# SCNUC51V2.net
KiCad netlist of a schematic drawn in Altium Designer
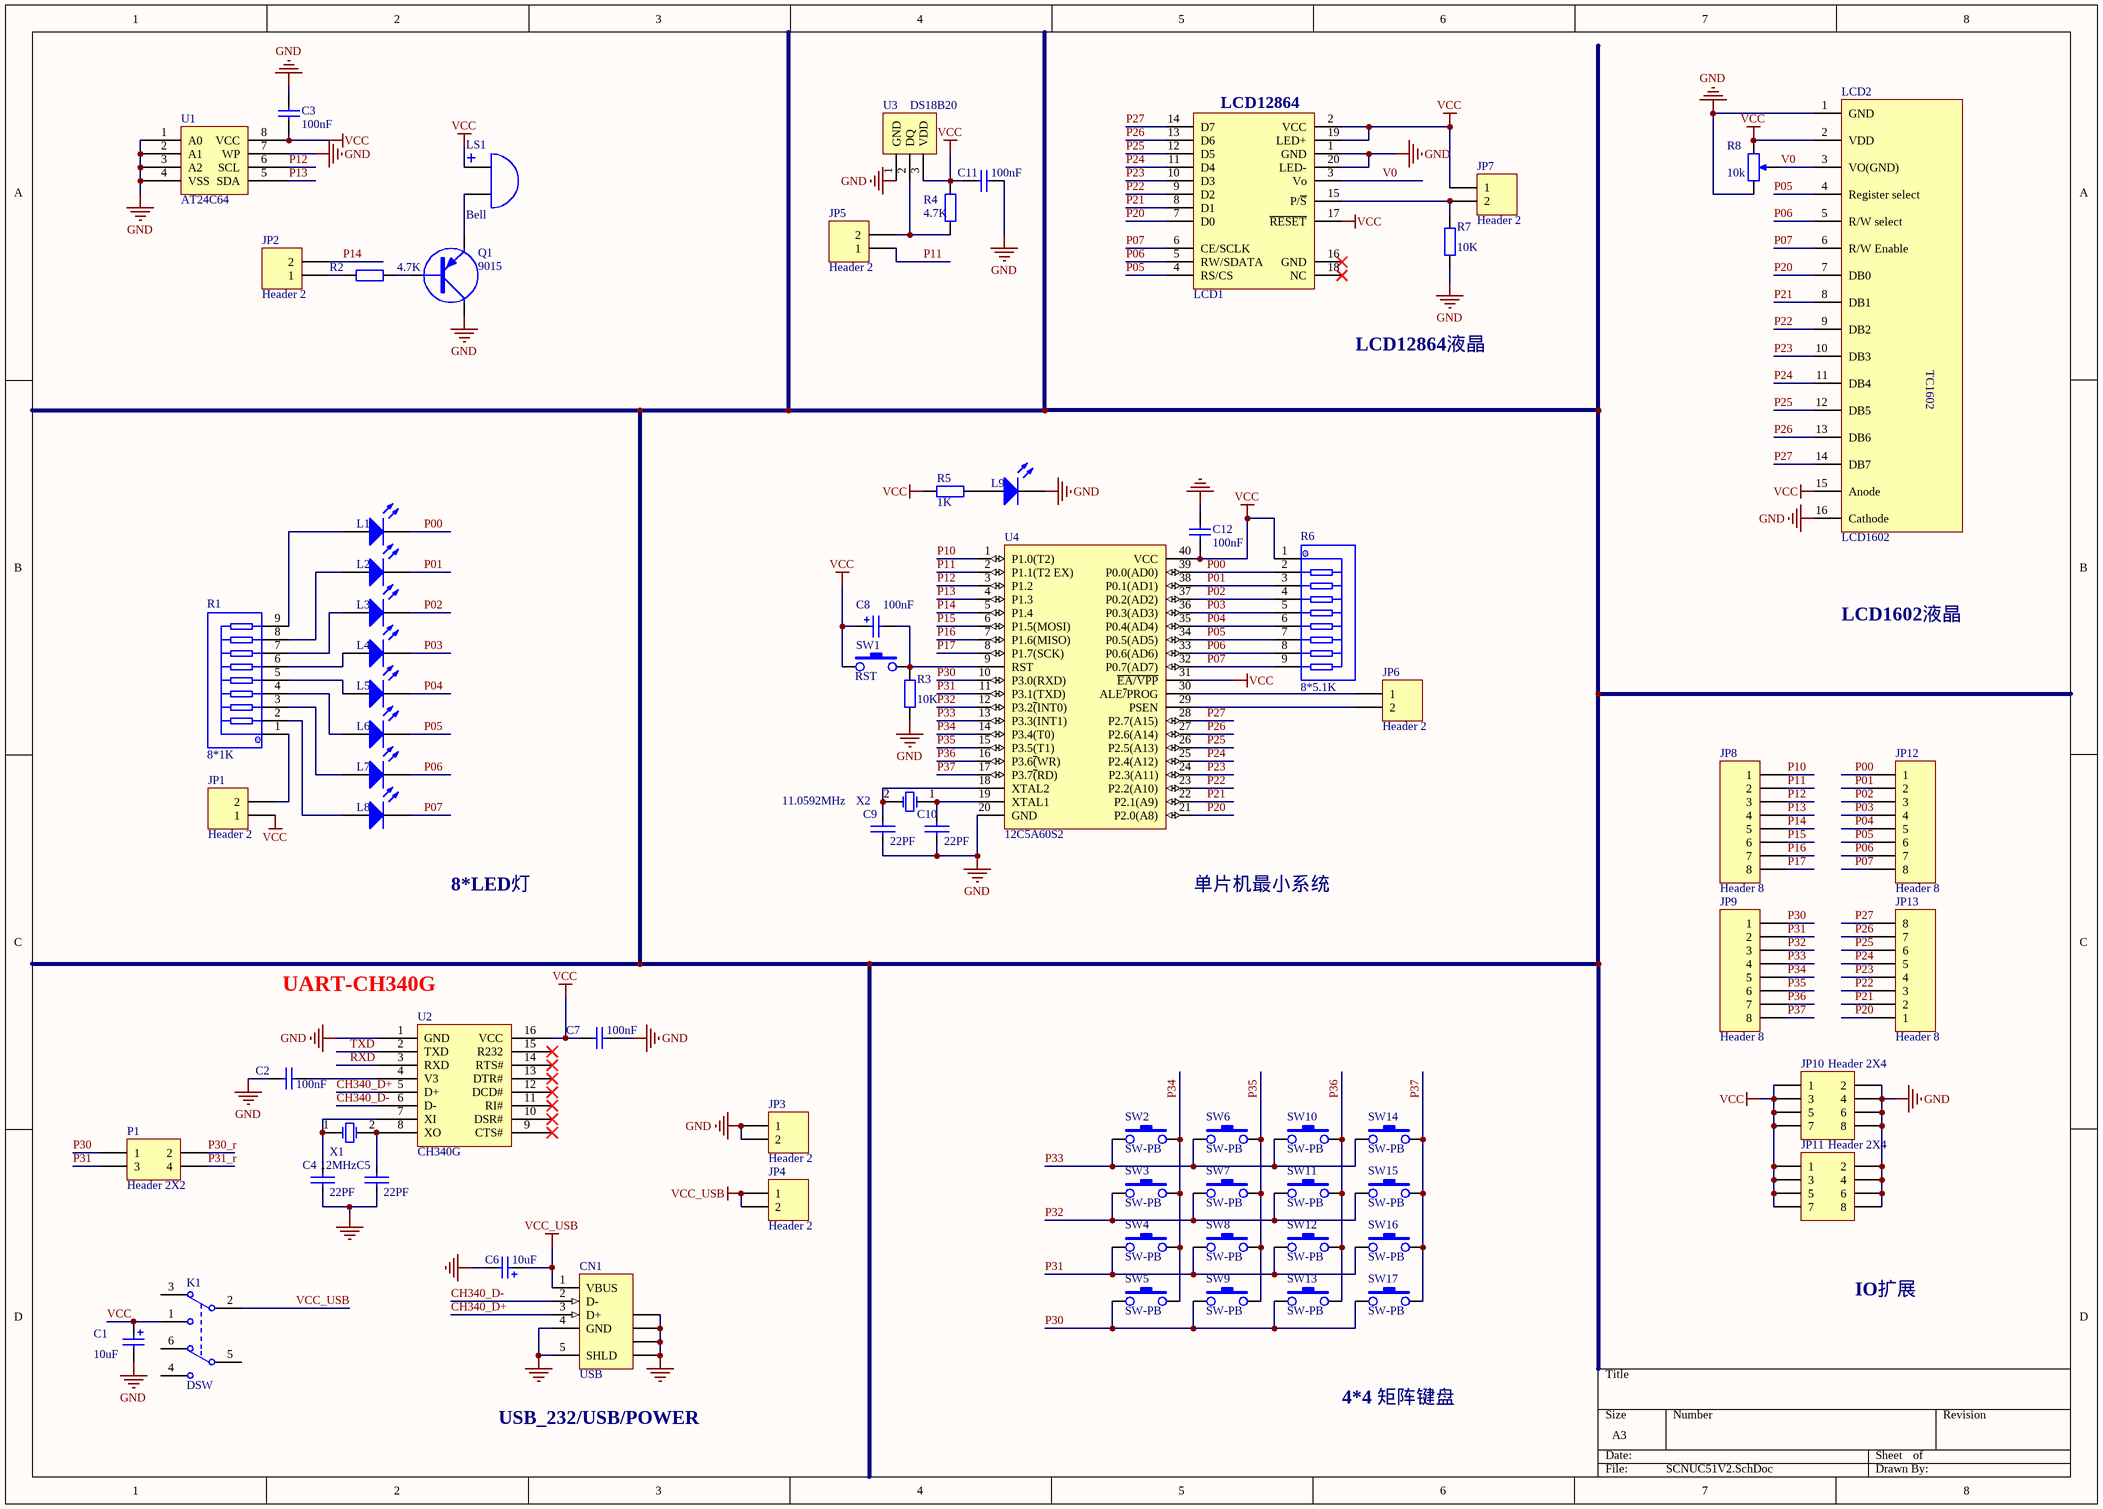
[diagram p0: SCNUC51V2.SchDoc]

(export (version "E")
  (design (tool "Eeschema 10.0.6"))
  (components
    (comp (ref "C1")
      (value "10uF")
      (footprint "hecheng:RB0.1-0.2")
      (description "Capacitor")
      (fields
        (field (name "MANUFACTURER") "Generic Components")
        (field (name "Comment") "Cap")
        (field (name "PUBLISHER") "Altium Hobart Technology Centre")
      )
      (libsource (lib "hecheng") (part "Cap Pol1"))
    )
    (comp (ref "C2")
      (value "100nF")
      (footprint "C0805")
      (description "Capacitor")
      (fields (field (name "Comment") "Cap"))
      (libsource (lib "Myself") (part "Cap"))
    )
    (comp (ref "C3")
      (value "100nF")
      (footprint "C0805")
      (description "Capacitor")
      (fields (field (name "Comment") "Cap"))
      (libsource (lib "Myself") (part "Cap"))
    )
    (comp (ref "C4")
      (value "22PF")
      (footprint "C0805")
      (description "Capacitor")
      (fields (field (name "Comment") "CAP"))
      (libsource (lib "hecheng") (part "CAP"))
    )
    (comp (ref "C5")
      (value "22PF")
      (footprint "C0805")
      (description "Capacitor")
      (fields (field (name "Comment") "CAP"))
      (libsource (lib "hecheng") (part "CAP"))
    )
    (comp (ref "C6")
      (value "10uF")
      (footprint "RB0.1-0.2")
      (description "Capacitor")
      (fields
        (field (name "MANUFACTURER") "Generic Components")
        (field (name "Comment") "Cap")
        (field (name "PUBLISHER") "Altium Hobart Technology Centre")
      )
      (libsource (lib "hecheng") (part "Cap Pol1"))
    )
    (comp (ref "C7")
      (value "100nF")
      (footprint "C0805")
      (description "Capacitor")
      (fields (field (name "Comment") "Cap"))
      (libsource (lib "Myself") (part "Cap"))
    )
    (comp (ref "C8")
      (value "100nF")
      (footprint "C0805")
      (description "Capacitor")
      (fields
        (field (name "MANUFACTURER") "Generic Components")
        (field (name "Comment") "CAP")
        (field (name "PUBLISHER") "Altium Hobart Technology Centre")
      )
      (libsource (lib "hecheng") (part "Cap Pol1"))
    )
    (comp (ref "C9")
      (value "22PF")
      (footprint "C0805")
      (description "Capacitor")
      (fields (field (name "Comment") "CAP"))
      (libsource (lib "hecheng") (part "CAP"))
    )
    (comp (ref "C10")
      (value "22PF")
      (footprint "C0805")
      (description "Capacitor")
      (fields (field (name "Comment") "CAP"))
      (libsource (lib "hecheng") (part "CAP"))
    )
    (comp (ref "C11")
      (value "100nF")
      (footprint "C0805")
      (description "Capacitor")
      (fields (field (name "Comment") "Cap"))
      (libsource (lib "Myself") (part "Cap"))
    )
    (comp (ref "C12")
      (value "100nF")
      (footprint "C0805")
      (description "Capacitor")
      (fields (field (name "Comment") "Cap"))
      (libsource (lib "Myself") (part "Cap"))
    )
    (comp (ref "CN1")
      (value "USB")
      (footprint "USB-mini")
      (description "USB MINI")
      (fields (field (name "PUBLISHER") "Altium Limited"))
      (libsource (lib "AMP Serial Bus USB") (part "440479-1"))
    )
    (comp (ref "JP1")
      (value "Header 2")
      (footprint "HDR1X2")
      (description "Header, 2-Pin")
      (fields (field (name "PUBLISHER") "Altium Limited"))
      (libsource (lib "") (part "Header 2_1"))
    )
    (comp (ref "JP2")
      (value "Header 2")
      (footprint "HDR1X2")
      (description "Header, 2-Pin")
      (fields (field (name "PUBLISHER") "Altium Limited"))
      (libsource (lib "") (part "Header 2_1"))
    )
    (comp (ref "JP3")
      (value "Header 2")
      (footprint "HDR1X2")
      (description "Header, 2-Pin")
      (fields (field (name "PUBLISHER") "Altium Limited"))
      (libsource (lib "hecheng") (part "Header 2"))
    )
    (comp (ref "JP4")
      (value "Header 2")
      (footprint "HDR1X2")
      (description "Header, 2-Pin")
      (fields (field (name "PUBLISHER") "Altium Limited"))
      (libsource (lib "hecheng") (part "Header 2"))
    )
    (comp (ref "JP5")
      (value "Header 2")
      (footprint "HDR1X2")
      (description "Header, 2-Pin")
      (fields (field (name "PUBLISHER") "Altium Limited"))
      (libsource (lib "") (part "Header 2_1"))
    )
    (comp (ref "JP6")
      (value "Header 2")
      (footprint "HDR1X2")
      (description "Header, 2-Pin")
      (fields (field (name "PUBLISHER") "Altium Limited"))
      (libsource (lib "hecheng") (part "Header 2"))
    )
    (comp (ref "JP7")
      (value "Header 2")
      (footprint "HDR1X2")
      (description "Header, 2-Pin")
      (fields (field (name "PUBLISHER") "Altium Limited"))
      (libsource (lib "hecheng") (part "Header 2"))
    )
    (comp (ref "JP8")
      (value "Header 8")
      (footprint "HDR1X8")
      (description "Header, 8-Pin")
      (fields (field (name "PUBLISHER") "Altium Limited"))
      (libsource (lib "") (part "Header 8_2"))
    )
    (comp (ref "JP9")
      (value "Header 8")
      (footprint "HDR1X8")
      (description "Header, 8-Pin")
      (fields (field (name "PUBLISHER") "Altium Limited"))
      (libsource (lib "") (part "Header 8_2"))
    )
    (comp (ref "JP10")
      (value "Header 2X4")
      (footprint "HDR2-4")
      (description "Header, 4-Pin, Dual row")
      (fields (field (name "MANUFACTURER") "Generic Components"))
      (libsource (lib "hecheng") (part "Header 2X4"))
    )
    (comp (ref "JP11")
      (value "Header 2X4")
      (footprint "HDR2-4")
      (description "Header, 4-Pin, Dual row")
      (fields (field (name "MANUFACTURER") "Generic Components"))
      (libsource (lib "hecheng") (part "Header 2X4"))
    )
    (comp (ref "JP12")
      (value "Header 8")
      (footprint "HDR1X8")
      (description "Header, 8-Pin")
      (fields (field (name "PUBLISHER") "Altium Limited"))
      (libsource (lib "") (part "Header 8_1"))
    )
    (comp (ref "JP13")
      (value "Header 8")
      (footprint "HDR1X8")
      (description "Header, 8-Pin")
      (fields (field (name "PUBLISHER") "Altium Limited"))
      (libsource (lib "hecheng") (part "Header 8"))
    )
    (comp (ref "K1") (value "DSW") (footprint "DPDT-6") (libsource (lib "hecheng") (part "DSW")))
    (comp (ref "L1") (value "LED") (footprint "LED-3MM") (libsource (lib "hecheng") (part "LED-3MM")))
    (comp (ref "L2") (value "LED") (footprint "LED-3MM") (libsource (lib "hecheng") (part "LED-3MM")))
    (comp (ref "L3") (value "LED") (footprint "LED-3MM") (libsource (lib "hecheng") (part "LED-3MM")))
    (comp (ref "L4") (value "LED") (footprint "LED-3MM") (libsource (lib "hecheng") (part "LED-3MM")))
    (comp (ref "L5") (value "LED") (footprint "LED-3MM") (libsource (lib "hecheng") (part "LED-3MM")))
    (comp (ref "L6") (value "LED") (footprint "LED-3MM") (libsource (lib "hecheng") (part "LED-3MM")))
    (comp (ref "L7") (value "LED") (footprint "LED-3MM") (libsource (lib "hecheng") (part "LED-3MM")))
    (comp (ref "L8") (value "LED") (footprint "LED-3MM") (libsource (lib "hecheng") (part "LED-3MM")))
    (comp (ref "L9") (value "LED") (footprint "LED-3MM") (libsource (lib "hecheng") (part "LED-3MM")))
    (comp (ref "LCD1")
      (value "LCD12864")
      (footprint "LCD12864F")
      (libsource (lib "SXF'S LIB") (part "LCD12864"))
    )
    (comp (ref "LCD2") (value "LCD1602") (footprint "LCD1602") (libsource (lib "hecheng") (part "LCD1602")))
    (comp (ref "LS1")
      (value "Bell")
      (footprint "BELL0.3-0.46")
      (description "Electrical Bell")
      (fields (field (name "MANUFACTURER") "Generic Components"))
      (libsource (lib "hecheng") (part "Bell"))
    )
    (comp (ref "P1")
      (value "Header 2X2")
      (footprint "HDR2X2")
      (description "Header, 2-Pin, Dual row")
      (fields (field (name "PUBLISHER") "Altium Limited"))
      (libsource (lib "Miscellaneous Connectors") (part "Header 2X2"))
    )
    (comp (ref "Q1")
      (value "9015")
      (footprint "TO-92")
      (description "PNP")
      (libsource (lib "hecheng") (part "9015"))
    )
    (comp (ref "R1")
      (value "8*1K")
      (footprint "PIN-9")
      (description "Resistor Array")
      (fields (field (name "Comment") "RES-8"))
      (libsource (lib "hecheng") (part "RES-8"))
    )
    (comp (ref "R2")
      (value "4.7K")
      (footprint "SXF'S LIB:R0805")
      (description "Resistor")
      (fields
        (field (name "MANUFACTURER") "Generic Components")
        (field (name "Comment") "Res")
        (field (name "PUBLISHER") "Altium Hobart Technology Centre")
      )
      (libsource (lib "hecheng") (part "Res"))
    )
    (comp (ref "R3")
      (value "10K")
      (footprint "hecheng:R0805")
      (description "Resistor")
      (fields
        (field (name "MANUFACTURER") "Generic Components")
        (field (name "Comment") "Res")
        (field (name "PUBLISHER") "Altium Hobart Technology Centre")
      )
      (libsource (lib "") (part "Res_1"))
    )
    (comp (ref "R4")
      (value "4.7K")
      (footprint "R0805")
      (description "Resistor")
      (fields
        (field (name "MANUFACTURER") "Generic Components")
        (field (name "Comment") "Res")
        (field (name "PUBLISHER") "Altium Hobart Technology Centre")
      )
      (libsource (lib "") (part "Res_2"))
    )
    (comp (ref "R5")
      (value "1K")
      (footprint "R0805")
      (description "Resistor")
      (fields
        (field (name "MANUFACTURER") "Generic Components")
        (field (name "Comment") "Res")
        (field (name "PUBLISHER") "Altium Hobart Technology Centre")
      )
      (libsource (lib "hecheng") (part "Res"))
    )
    (comp (ref "R6")
      (value "8*5.1K")
      (footprint "PIN-9")
      (description "Resistor Array")
      (fields (field (name "Comment") "RES-8"))
      (libsource (lib "hecheng") (part "RES-8"))
    )
    (comp (ref "R7")
      (value "10K")
      (footprint "hecheng:R0805")
      (description "Resistor")
      (fields
        (field (name "MANUFACTURER") "Generic Components")
        (field (name "Comment") "Res")
        (field (name "PUBLISHER") "Altium Hobart Technology Centre")
      )
      (libsource (lib "") (part "Res_1"))
    )
    (comp (ref "R8")
      (value "10k")
      (footprint "hecheng:VR-Z")
      (description "Potentiometer")
      (fields (field (name "Comment") "RES-Pot2"))
      (libsource (lib "hecheng") (part "RES-Pot2"))
    )
    (comp (ref "SW1")
      (value "RST")
      (footprint "SW1")
      (description "Button")
      (libsource (lib "hecheng") (part "SW-PB"))
    )
    (comp (ref "SW2") (value "SW-PB") (footprint "SW1") (libsource (lib "hecheng") (part "SW-PB")))
    (comp (ref "SW3") (value "SW-PB") (footprint "SW1") (libsource (lib "hecheng") (part "SW-PB")))
    (comp (ref "SW4") (value "SW-PB") (footprint "SW1") (libsource (lib "hecheng") (part "SW-PB")))
    (comp (ref "SW5") (value "SW-PB") (footprint "SW1") (libsource (lib "hecheng") (part "SW-PB")))
    (comp (ref "SW6") (value "SW-PB") (footprint "SW1") (libsource (lib "hecheng") (part "SW-PB")))
    (comp (ref "SW7") (value "SW-PB") (footprint "SW1") (libsource (lib "hecheng") (part "SW-PB")))
    (comp (ref "SW8") (value "SW-PB") (footprint "SW1") (libsource (lib "hecheng") (part "SW-PB")))
    (comp (ref "SW9") (value "SW-PB") (footprint "SW1") (libsource (lib "hecheng") (part "SW-PB")))
    (comp (ref "SW10") (value "SW-PB") (footprint "SW1") (libsource (lib "hecheng") (part "SW-PB")))
    (comp (ref "SW11") (value "SW-PB") (footprint "SW1") (libsource (lib "hecheng") (part "SW-PB")))
    (comp (ref "SW12") (value "SW-PB") (footprint "SW1") (libsource (lib "hecheng") (part "SW-PB")))
    (comp (ref "SW13") (value "SW-PB") (footprint "SW1") (libsource (lib "hecheng") (part "SW-PB")))
    (comp (ref "SW14") (value "SW-PB") (footprint "SW1") (libsource (lib "hecheng") (part "SW-PB")))
    (comp (ref "SW15") (value "SW-PB") (footprint "SW1") (libsource (lib "hecheng") (part "SW-PB")))
    (comp (ref "SW16") (value "SW-PB") (footprint "SW1") (libsource (lib "hecheng") (part "SW-PB")))
    (comp (ref "SW17") (value "SW-PB") (footprint "SW1") (libsource (lib "hecheng") (part "SW-PB")))
    (comp (ref "U1") (value "AT24C64") (footprint "DIP-8") (libsource (lib "hecheng") (part "AT24C64")))
    (comp (ref "U2")
      (value "CH340G")
      (footprint "SOP-127-16M")
      (description "USBtoUART")
      (libsource (lib "Myself") (part "CH340G"))
    )
    (comp (ref "U3")
      (value "DS18B20")
      (footprint "BCY-3")
      (description "Programmable Resolution\r\n1-Wire Digital Thermometer")
      (libsource (lib "hecheng") (part "DS18B20"))
    )
    (comp (ref "U4") (value "12C5A60S2") (footprint "DIP-40") (libsource (lib "hecheng") (part "89c51")))
    (comp (ref "X1")
      (value "12MHz")
      (footprint "XTAL")
      (description "XTAL")
      (libsource (lib "Myself") (part "XTAL"))
    )
    (comp (ref "X2")
      (value "11.0592MHz")
      (footprint "XTAL")
      (fields (field (name "Comment") "XTAL"))
      (libsource (lib "hecheng") (part "XTAL"))
    )
  )
  (nets
    (net (code "1") (name "/CH340_D+") (class "Default")
      (node (ref "CN1") (pin "3") (pinfunction "D+_3") (pintype "input"))
      (node (ref "U2") (pin "5") (pinfunction "D+_5") (pintype "passive"))
    )
    (net (code "2") (name "/CH340_D-") (class "Default")
      (node (ref "CN1") (pin "2") (pinfunction "D-_2") (pintype "input"))
      (node (ref "U2") (pin "6") (pinfunction "D-_6") (pintype "passive"))
    )
    (net (code "3") (name "/P00") (class "Default")
      (node (ref "JP12") (pin "1") (pinfunction "1_1") (pintype "passive"))
      (node (ref "L1") (pin "2") (pinfunction "K_2") (pintype "passive"))
      (node (ref "R6") (pin "2") (pinfunction "2_2") (pintype "passive"))
      (node (ref "U4") (pin "39") (pinfunction "P0.0(AD0)_39") (pintype "bidirectional"))
    )
    (net (code "4") (name "/P01") (class "Default")
      (node (ref "JP12") (pin "2") (pinfunction "2_2") (pintype "passive"))
      (node (ref "L2") (pin "2") (pinfunction "K_2") (pintype "passive"))
      (node (ref "R6") (pin "3") (pinfunction "3_3") (pintype "passive"))
      (node (ref "U4") (pin "38") (pinfunction "P0.1(AD1)_38") (pintype "bidirectional"))
    )
    (net (code "5") (name "/P02") (class "Default")
      (node (ref "JP12") (pin "3") (pinfunction "3_3") (pintype "passive"))
      (node (ref "L3") (pin "2") (pinfunction "K_2") (pintype "passive"))
      (node (ref "R6") (pin "4") (pinfunction "4_4") (pintype "passive"))
      (node (ref "U4") (pin "37") (pinfunction "P0.2(AD2)_37") (pintype "bidirectional"))
    )
    (net (code "6") (name "/P03") (class "Default")
      (node (ref "JP12") (pin "4") (pinfunction "4_4") (pintype "passive"))
      (node (ref "L4") (pin "2") (pinfunction "K_2") (pintype "passive"))
      (node (ref "R6") (pin "5") (pinfunction "5_5") (pintype "passive"))
      (node (ref "U4") (pin "36") (pinfunction "P0.3(AD3)_36") (pintype "bidirectional"))
    )
    (net (code "7") (name "/P04") (class "Default")
      (node (ref "JP12") (pin "5") (pinfunction "5_5") (pintype "passive"))
      (node (ref "L5") (pin "2") (pinfunction "K_2") (pintype "passive"))
      (node (ref "R6") (pin "6") (pinfunction "6_6") (pintype "passive"))
      (node (ref "U4") (pin "35") (pinfunction "P0.4(AD4)_35") (pintype "bidirectional"))
    )
    (net (code "8") (name "/P05") (class "Default")
      (node (ref "JP12") (pin "6") (pinfunction "6_6") (pintype "passive"))
      (node (ref "L6") (pin "2") (pinfunction "K_2") (pintype "passive"))
      (node (ref "LCD1") (pin "4") (pinfunction "RS/CS_4") (pintype "passive"))
      (node (ref "LCD2") (pin "4") (pinfunction "Register_select_4") (pintype "passive"))
      (node (ref "R6") (pin "7") (pinfunction "7_7") (pintype "passive"))
      (node (ref "U4") (pin "34") (pinfunction "P0.5(AD5)_34") (pintype "bidirectional"))
    )
    (net (code "9") (name "/P06") (class "Default")
      (node (ref "JP12") (pin "7") (pinfunction "7_7") (pintype "passive"))
      (node (ref "L7") (pin "2") (pinfunction "K_2") (pintype "passive"))
      (node (ref "LCD1") (pin "5") (pinfunction "RW/SDATA_5") (pintype "passive"))
      (node (ref "LCD2") (pin "5") (pinfunction "R/W_select_5") (pintype "passive"))
      (node (ref "R6") (pin "8") (pinfunction "8_8") (pintype "passive"))
      (node (ref "U4") (pin "33") (pinfunction "P0.6(AD6)_33") (pintype "bidirectional"))
    )
    (net (code "10") (name "/P07") (class "Default")
      (node (ref "JP12") (pin "8") (pinfunction "8_8") (pintype "passive"))
      (node (ref "L8") (pin "2") (pinfunction "K_2") (pintype "passive"))
      (node (ref "LCD1") (pin "6") (pinfunction "CE/SCLK_6") (pintype "passive"))
      (node (ref "LCD2") (pin "6") (pinfunction "R/W_Enable_6") (pintype "passive"))
      (node (ref "R6") (pin "9") (pinfunction "9_9") (pintype "passive"))
      (node (ref "U4") (pin "32") (pinfunction "P0.7(AD7)_32") (pintype "bidirectional"))
    )
    (net (code "11") (name "/P10") (class "Default")
      (node (ref "JP8") (pin "1") (pinfunction "1_1") (pintype "passive"))
      (node (ref "U4") (pin "1") (pinfunction "P1.0(T2)_1") (pintype "bidirectional"))
    )
    (net (code "12") (name "/P11") (class "Default")
      (node (ref "JP5") (pin "1") (pinfunction "1_1") (pintype "passive"))
      (node (ref "JP8") (pin "2") (pinfunction "2_2") (pintype "passive"))
      (node (ref "U4") (pin "2") (pinfunction "P1.1(T2_EX)_2") (pintype "bidirectional"))
    )
    (net (code "13") (name "/P12") (class "Default")
      (node (ref "JP8") (pin "3") (pinfunction "3_3") (pintype "passive"))
      (node (ref "U1") (pin "6") (pinfunction "SCL_6") (pintype "passive"))
      (node (ref "U4") (pin "3") (pinfunction "P1.2_3") (pintype "bidirectional"))
    )
    (net (code "14") (name "/P13") (class "Default")
      (node (ref "JP8") (pin "4") (pinfunction "4_4") (pintype "passive"))
      (node (ref "U1") (pin "5") (pinfunction "SDA_5") (pintype "passive"))
      (node (ref "U4") (pin "4") (pinfunction "P1.3_4") (pintype "bidirectional"))
    )
    (net (code "15") (name "/P14") (class "Default")
      (node (ref "JP2") (pin "2") (pinfunction "2_2") (pintype "passive"))
      (node (ref "JP8") (pin "5") (pinfunction "5_5") (pintype "passive"))
      (node (ref "U4") (pin "5") (pinfunction "P1.4_5") (pintype "bidirectional"))
    )
    (net (code "16") (name "/P15") (class "Default")
      (node (ref "JP8") (pin "6") (pinfunction "6_6") (pintype "passive"))
      (node (ref "U4") (pin "6") (pinfunction "P1.5(MOSI)_6") (pintype "bidirectional"))
    )
    (net (code "17") (name "/P16") (class "Default")
      (node (ref "JP8") (pin "7") (pinfunction "7_7") (pintype "passive"))
      (node (ref "U4") (pin "7") (pinfunction "P1.6(MISO)_7") (pintype "bidirectional"))
    )
    (net (code "18") (name "/P17") (class "Default")
      (node (ref "JP8") (pin "8") (pinfunction "8_8") (pintype "passive"))
      (node (ref "U4") (pin "8") (pinfunction "P1.7(SCK)_8") (pintype "bidirectional"))
    )
    (net (code "19") (name "/P20") (class "Default")
      (node (ref "JP13") (pin "1") (pinfunction "1_1") (pintype "passive"))
      (node (ref "LCD1") (pin "7") (pinfunction "D0_7") (pintype "passive"))
      (node (ref "LCD2") (pin "7") (pinfunction "DB0_7") (pintype "passive"))
      (node (ref "U4") (pin "21") (pinfunction "P2.0(A8)_21") (pintype "bidirectional"))
    )
    (net (code "20") (name "/P21") (class "Default")
      (node (ref "JP13") (pin "2") (pinfunction "2_2") (pintype "passive"))
      (node (ref "LCD1") (pin "8") (pinfunction "D1_8") (pintype "passive"))
      (node (ref "LCD2") (pin "8") (pinfunction "DB1_8") (pintype "passive"))
      (node (ref "U4") (pin "22") (pinfunction "P2.1(A9)_22") (pintype "bidirectional"))
    )
    (net (code "21") (name "/P22") (class "Default")
      (node (ref "JP13") (pin "3") (pinfunction "3_3") (pintype "passive"))
      (node (ref "LCD1") (pin "9") (pinfunction "D2_9") (pintype "passive"))
      (node (ref "LCD2") (pin "9") (pinfunction "DB2_9") (pintype "passive"))
      (node (ref "U4") (pin "23") (pinfunction "P2.2(A10)_23") (pintype "bidirectional"))
    )
    (net (code "22") (name "/P23") (class "Default")
      (node (ref "JP13") (pin "4") (pinfunction "4_4") (pintype "passive"))
      (node (ref "LCD1") (pin "10") (pinfunction "D3_10") (pintype "passive"))
      (node (ref "LCD2") (pin "10") (pinfunction "DB3_10") (pintype "passive"))
      (node (ref "U4") (pin "24") (pinfunction "P2.3(A11)_24") (pintype "bidirectional"))
    )
    (net (code "23") (name "/P24") (class "Default")
      (node (ref "JP13") (pin "5") (pinfunction "5_5") (pintype "passive"))
      (node (ref "LCD1") (pin "11") (pinfunction "D4_11") (pintype "passive"))
      (node (ref "LCD2") (pin "11") (pinfunction "DB4_11") (pintype "passive"))
      (node (ref "U4") (pin "25") (pinfunction "P2.4(A12)_25") (pintype "bidirectional"))
    )
    (net (code "24") (name "/P25") (class "Default")
      (node (ref "JP13") (pin "6") (pinfunction "6_6") (pintype "passive"))
      (node (ref "LCD1") (pin "12") (pinfunction "D5_12") (pintype "passive"))
      (node (ref "LCD2") (pin "12") (pinfunction "DB5_12") (pintype "passive"))
      (node (ref "U4") (pin "26") (pinfunction "P2.5(A13)_26") (pintype "bidirectional"))
    )
    (net (code "25") (name "/P26") (class "Default")
      (node (ref "JP13") (pin "7") (pinfunction "7_7") (pintype "passive"))
      (node (ref "LCD1") (pin "13") (pinfunction "D6_13") (pintype "passive"))
      (node (ref "LCD2") (pin "13") (pinfunction "DB6_13") (pintype "passive"))
      (node (ref "U4") (pin "27") (pinfunction "P2.6(A14)_27") (pintype "bidirectional"))
    )
    (net (code "26") (name "/P27") (class "Default")
      (node (ref "JP13") (pin "8") (pinfunction "8_8") (pintype "passive"))
      (node (ref "LCD1") (pin "14") (pinfunction "D7_14") (pintype "passive"))
      (node (ref "LCD2") (pin "14") (pinfunction "DB7_14") (pintype "passive"))
      (node (ref "U4") (pin "28") (pinfunction "P2.7(A15)_28") (pintype "bidirectional"))
    )
    (net (code "27") (name "/P30") (class "Default")
      (node (ref "JP9") (pin "1") (pinfunction "1_1") (pintype "passive"))
      (node (ref "P1") (pin "1") (pinfunction "1_1") (pintype "passive"))
      (node (ref "SW13") (pin "1") (pintype "passive"))
      (node (ref "SW17") (pin "1") (pintype "passive"))
      (node (ref "SW5") (pin "1") (pintype "passive"))
      (node (ref "SW9") (pin "1") (pintype "passive"))
      (node (ref "U4") (pin "10") (pinfunction "P3.0(RXD)_10") (pintype "bidirectional"))
    )
    (net (code "28") (name "/P30_r") (class "Default")
      (node (ref "P1") (pin "2") (pinfunction "2_2") (pintype "passive"))
    )
    (net (code "29") (name "/P31") (class "Default")
      (node (ref "JP9") (pin "2") (pinfunction "2_2") (pintype "passive"))
      (node (ref "P1") (pin "3") (pinfunction "3_3") (pintype "passive"))
      (node (ref "SW12") (pin "1") (pintype "passive"))
      (node (ref "SW16") (pin "1") (pintype "passive"))
      (node (ref "SW4") (pin "1") (pintype "passive"))
      (node (ref "SW8") (pin "1") (pintype "passive"))
      (node (ref "U4") (pin "11") (pinfunction "P3.1(TXD)_11") (pintype "bidirectional"))
    )
    (net (code "30") (name "/P31_r") (class "Default")
      (node (ref "P1") (pin "4") (pinfunction "4_4") (pintype "passive"))
    )
    (net (code "31") (name "/P32") (class "Default")
      (node (ref "JP9") (pin "3") (pinfunction "3_3") (pintype "passive"))
      (node (ref "SW11") (pin "1") (pintype "passive"))
      (node (ref "SW15") (pin "1") (pintype "passive"))
      (node (ref "SW3") (pin "1") (pintype "passive"))
      (node (ref "SW7") (pin "1") (pintype "passive"))
      (node (ref "U4") (pin "12") (pinfunction "P3.2~{(}INT0)_12") (pintype "bidirectional"))
    )
    (net (code "32") (name "/P33") (class "Default")
      (node (ref "JP9") (pin "4") (pinfunction "4_4") (pintype "passive"))
      (node (ref "SW10") (pin "1") (pintype "passive"))
      (node (ref "SW14") (pin "1") (pintype "passive"))
      (node (ref "SW2") (pin "1") (pintype "passive"))
      (node (ref "SW6") (pin "1") (pintype "passive"))
      (node (ref "U4") (pin "13") (pinfunction "P3.3(INT1)_13") (pintype "bidirectional"))
    )
    (net (code "33") (name "/P34") (class "Default")
      (node (ref "JP9") (pin "5") (pinfunction "5_5") (pintype "passive"))
      (node (ref "SW2") (pin "2") (pintype "passive"))
      (node (ref "SW3") (pin "2") (pintype "passive"))
      (node (ref "SW4") (pin "2") (pintype "passive"))
      (node (ref "SW5") (pin "2") (pintype "passive"))
      (node (ref "U4") (pin "14") (pinfunction "P3.4(T0)_14") (pintype "bidirectional"))
    )
    (net (code "34") (name "/P35") (class "Default")
      (node (ref "JP9") (pin "6") (pinfunction "6_6") (pintype "passive"))
      (node (ref "SW6") (pin "2") (pintype "passive"))
      (node (ref "SW7") (pin "2") (pintype "passive"))
      (node (ref "SW8") (pin "2") (pintype "passive"))
      (node (ref "SW9") (pin "2") (pintype "passive"))
      (node (ref "U4") (pin "15") (pinfunction "P3.5(T1)_15") (pintype "bidirectional"))
    )
    (net (code "35") (name "/P36") (class "Default")
      (node (ref "JP9") (pin "7") (pinfunction "7_7") (pintype "passive"))
      (node (ref "SW10") (pin "2") (pintype "passive"))
      (node (ref "SW11") (pin "2") (pintype "passive"))
      (node (ref "SW12") (pin "2") (pintype "passive"))
      (node (ref "SW13") (pin "2") (pintype "passive"))
      (node (ref "U4") (pin "16") (pinfunction "P3.6~{(}WR)_16") (pintype "bidirectional"))
    )
    (net (code "36") (name "/P37") (class "Default")
      (node (ref "JP9") (pin "8") (pinfunction "8_8") (pintype "passive"))
      (node (ref "SW14") (pin "2") (pintype "passive"))
      (node (ref "SW15") (pin "2") (pintype "passive"))
      (node (ref "SW16") (pin "2") (pintype "passive"))
      (node (ref "SW17") (pin "2") (pintype "passive"))
      (node (ref "U4") (pin "17") (pinfunction "P3.7~{(}RD)_17") (pintype "bidirectional"))
    )
    (net (code "37") (name "/RXD") (class "Default")
      (node (ref "U2") (pin "3") (pinfunction "RXD_3") (pintype "passive"))
    )
    (net (code "38") (name "/TXD") (class "Default")
      (node (ref "U2") (pin "2") (pinfunction "TXD_2") (pintype "passive"))
    )
    (net (code "39") (name "/V0") (class "Default")
      (node (ref "LCD1") (pin "3") (pinfunction "Vo_3") (pintype "passive"))
      (node (ref "LCD2") (pin "3") (pinfunction "VO(GND)_3") (pintype "passive"))
      (node (ref "R8") (pin "2") (pinfunction "TAP_2") (pintype "passive"))
    )
    (net (code "40") (name "GND") (class "Default")
      (node (ref "C1") (pin "2") (pinfunction "2_2") (pintype "passive"))
      (node (ref "C10") (pin "1") (pintype "passive"))
      (node (ref "C11") (pin "2") (pinfunction "2_2") (pintype "passive"))
      (node (ref "C12") (pin "2") (pinfunction "2_2") (pintype "passive"))
      (node (ref "C2") (pin "1") (pinfunction "1_1") (pintype "passive"))
      (node (ref "C3") (pin "2") (pinfunction "2_2") (pintype "passive"))
      (node (ref "C4") (pin "1") (pintype "passive"))
      (node (ref "C5") (pin "1") (pintype "passive"))
      (node (ref "C6") (pin "2") (pinfunction "2_2") (pintype "passive"))
      (node (ref "C7") (pin "2") (pinfunction "2_2") (pintype "passive"))
      (node (ref "C9") (pin "1") (pintype "passive"))
      (node (ref "CN1") (pin "4") (pinfunction "GND_4") (pintype "power_in"))
      (node (ref "CN1") (pin "5") (pinfunction "SHLD_5") (pintype "passive"))
      (node (ref "CN1") (pin "6") (pinfunction "SHLD_6") (pintype "passive"))
      (node (ref "CN1") (pin "7") (pinfunction "SHLD_7") (pintype "passive"))
      (node (ref "CN1") (pin "8") (pinfunction "SHLD_8") (pintype "passive"))
      (node (ref "CN1") (pin "9") (pinfunction "SHLD_9") (pintype "passive"))
      (node (ref "JP10") (pin "2") (pinfunction "2_2") (pintype "passive"))
      (node (ref "JP10") (pin "4") (pinfunction "4_4") (pintype "passive"))
      (node (ref "JP10") (pin "6") (pinfunction "6_6") (pintype "passive"))
      (node (ref "JP10") (pin "8") (pinfunction "8_8") (pintype "passive"))
      (node (ref "JP11") (pin "2") (pinfunction "2_2") (pintype "passive"))
      (node (ref "JP11") (pin "4") (pinfunction "4_4") (pintype "passive"))
      (node (ref "JP11") (pin "6") (pinfunction "6_6") (pintype "passive"))
      (node (ref "JP11") (pin "8") (pinfunction "8_8") (pintype "passive"))
      (node (ref "JP3") (pin "1") (pinfunction "1_1") (pintype "passive"))
      (node (ref "JP3") (pin "2") (pinfunction "2_2") (pintype "passive"))
      (node (ref "L9") (pin "2") (pinfunction "K_2") (pintype "passive"))
      (node (ref "LCD1") (pin "1") (pinfunction "GND_1") (pintype "passive"))
      (node (ref "LCD1") (pin "20") (pinfunction "LED-_20") (pintype "passive"))
      (node (ref "LCD2") (pin "1") (pinfunction "GND_1") (pintype "passive"))
      (node (ref "LCD2") (pin "16") (pinfunction "Cathode_16") (pintype "passive"))
      (node (ref "Q1") (pin "3") (pinfunction "C_3") (pintype "passive"))
      (node (ref "R3") (pin "1") (pinfunction "1_1") (pintype "passive"))
      (node (ref "R7") (pin "1") (pinfunction "1_1") (pintype "passive"))
      (node (ref "R8") (pin "3") (pinfunction "TOP_3") (pintype "passive"))
      (node (ref "U1") (pin "1") (pinfunction "A0_1") (pintype "passive"))
      (node (ref "U1") (pin "2") (pinfunction "A1_2") (pintype "passive"))
      (node (ref "U1") (pin "3") (pinfunction "A2_3") (pintype "passive"))
      (node (ref "U1") (pin "4") (pinfunction "VSS_4") (pintype "passive"))
      (node (ref "U1") (pin "7") (pinfunction "WP_7") (pintype "passive"))
      (node (ref "U2") (pin "1") (pinfunction "GND_1") (pintype "passive"))
      (node (ref "U3") (pin "1") (pinfunction "GND_1") (pintype "power_in"))
      (node (ref "U4") (pin "20") (pinfunction "GND_20") (pintype "passive"))
    )
    (net (code "41") (name "Net-(JP1-Pad2)") (class "Default")
      (node (ref "JP1") (pin "2") (pinfunction "2_2") (pintype "passive"))
      (node (ref "R1") (pin "1") (pinfunction "1_1") (pintype "passive"))
    )
    (net (code "42") (name "Net-(JP2-Pad1)") (class "Default")
      (node (ref "JP2") (pin "1") (pinfunction "1_1") (pintype "passive"))
      (node (ref "R2") (pin "1") (pinfunction "1_1") (pintype "passive"))
    )
    (net (code "43") (name "Net-(L1-A)") (class "Default")
      (node (ref "L1") (pin "1") (pinfunction "A_1") (pintype "passive"))
      (node (ref "R1") (pin "9") (pinfunction "9_9") (pintype "passive"))
    )
    (net (code "44") (name "Net-(L2-A)") (class "Default")
      (node (ref "L2") (pin "1") (pinfunction "A_1") (pintype "passive"))
      (node (ref "R1") (pin "8") (pinfunction "8_8") (pintype "passive"))
    )
    (net (code "45") (name "Net-(L3-A)") (class "Default")
      (node (ref "L3") (pin "1") (pinfunction "A_1") (pintype "passive"))
      (node (ref "R1") (pin "7") (pinfunction "7_7") (pintype "passive"))
    )
    (net (code "46") (name "Net-(L4-A)") (class "Default")
      (node (ref "L4") (pin "1") (pinfunction "A_1") (pintype "passive"))
      (node (ref "R1") (pin "6") (pinfunction "6_6") (pintype "passive"))
    )
    (net (code "47") (name "Net-(L5-A)") (class "Default")
      (node (ref "L5") (pin "1") (pinfunction "A_1") (pintype "passive"))
      (node (ref "R1") (pin "5") (pinfunction "5_5") (pintype "passive"))
    )
    (net (code "48") (name "Net-(L6-A)") (class "Default")
      (node (ref "L6") (pin "1") (pinfunction "A_1") (pintype "passive"))
      (node (ref "R1") (pin "4") (pinfunction "4_4") (pintype "passive"))
    )
    (net (code "49") (name "Net-(L7-A)") (class "Default")
      (node (ref "L7") (pin "1") (pinfunction "A_1") (pintype "passive"))
      (node (ref "R1") (pin "3") (pinfunction "3_3") (pintype "passive"))
    )
    (net (code "50") (name "Net-(L8-A)") (class "Default")
      (node (ref "L8") (pin "1") (pinfunction "A_1") (pintype "passive"))
      (node (ref "R1") (pin "2") (pinfunction "2_2") (pintype "passive"))
    )
    (net (code "51") (name "Net-(L9-A)") (class "Default")
      (node (ref "L9") (pin "1") (pinfunction "A_1") (pintype "passive"))
      (node (ref "R5") (pin "2") (pinfunction "2_2") (pintype "passive"))
    )
    (net (code "52") (name "Net-(LCD1-P{slash}~{S})") (class "Default")
      (node (ref "JP7") (pin "2") (pinfunction "2_2") (pintype "passive"))
      (node (ref "LCD1") (pin "15") (pinfunction "P/~{S}_15") (pintype "passive"))
      (node (ref "R7") (pin "2") (pinfunction "2_2") (pintype "passive"))
    )
    (net (code "53") (name "Net-(LS1-B)") (class "Default")
      (node (ref "LS1") (pin "2") (pinfunction "B_2") (pintype "passive"))
      (node (ref "Q1") (pin "1") (pinfunction "E_1") (pintype "passive"))
    )
    (net (code "54") (name "Net-(Q1-B)") (class "Default")
      (node (ref "Q1") (pin "2") (pinfunction "B_2") (pintype "passive"))
      (node (ref "R2") (pin "2") (pinfunction "2_2") (pintype "passive"))
    )
    (net (code "55") (name "Net-(U2-V3)") (class "Default")
      (node (ref "C2") (pin "2") (pinfunction "2_2") (pintype "passive"))
      (node (ref "U2") (pin "4") (pinfunction "V3_4") (pintype "passive"))
    )
    (net (code "56") (name "Net-(U2-XI)") (class "Default")
      (node (ref "C4") (pin "2") (pintype "passive"))
      (node (ref "U2") (pin "7") (pinfunction "XI_7") (pintype "passive"))
      (node (ref "X1") (pin "1") (pinfunction "OSC1_1") (pintype "passive"))
    )
    (net (code "57") (name "Net-(U2-XO)") (class "Default")
      (node (ref "C5") (pin "2") (pintype "passive"))
      (node (ref "U2") (pin "8") (pinfunction "XO_8") (pintype "passive"))
      (node (ref "X1") (pin "2") (pinfunction "OSC2_2") (pintype "passive"))
    )
    (net (code "58") (name "Net-(U3-DQ)") (class "Default")
      (node (ref "JP5") (pin "2") (pinfunction "2_2") (pintype "passive"))
      (node (ref "R4") (pin "2") (pinfunction "2_2") (pintype "passive"))
      (node (ref "U3") (pin "2") (pinfunction "DQ_2") (pintype "passive"))
    )
    (net (code "59") (name "Net-(U4-ALE~{{slash}}PROG)") (class "Default")
      (node (ref "JP6") (pin "1") (pinfunction "1_1") (pintype "passive"))
      (node (ref "U4") (pin "30") (pinfunction "ALE~{/}PROG_30") (pintype "passive"))
    )
    (net (code "60") (name "Net-(U4-PSEN)") (class "Default")
      (node (ref "JP6") (pin "2") (pinfunction "2_2") (pintype "passive"))
      (node (ref "U4") (pin "29") (pinfunction "PSEN_29") (pintype "passive"))
    )
    (net (code "61") (name "Net-(U4-RST)") (class "Default")
      (node (ref "C8") (pin "2") (pinfunction "2_2") (pintype "passive"))
      (node (ref "R3") (pin "2") (pinfunction "2_2") (pintype "passive"))
      (node (ref "SW1") (pin "2") (pintype "passive"))
      (node (ref "U4") (pin "9") (pinfunction "RST_9") (pintype "passive"))
    )
    (net (code "62") (name "Net-(U4-XTAL1)") (class "Default")
      (node (ref "C10") (pin "2") (pintype "passive"))
      (node (ref "U4") (pin "19") (pinfunction "XTAL1_19") (pintype "passive"))
      (node (ref "X2") (pin "1") (pinfunction "OSC1_1") (pintype "passive"))
    )
    (net (code "63") (name "Net-(U4-XTAL2)") (class "Default")
      (node (ref "C9") (pin "2") (pintype "passive"))
      (node (ref "U4") (pin "18") (pinfunction "XTAL2_18") (pintype "passive"))
      (node (ref "X2") (pin "2") (pinfunction "OSC2_2") (pintype "passive"))
    )
    (net (code "64") (name "VCC") (class "Default")
      (node (ref "C1") (pin "1") (pinfunction "1_1") (pintype "passive"))
      (node (ref "C11") (pin "1") (pinfunction "1_1") (pintype "passive"))
      (node (ref "C12") (pin "1") (pinfunction "1_1") (pintype "passive"))
      (node (ref "C3") (pin "1") (pinfunction "1_1") (pintype "passive"))
      (node (ref "C7") (pin "1") (pinfunction "1_1") (pintype "passive"))
      (node (ref "C8") (pin "1") (pinfunction "1_1") (pintype "passive"))
      (node (ref "JP1") (pin "1") (pinfunction "1_1") (pintype "passive"))
      (node (ref "JP10") (pin "1") (pinfunction "1_1") (pintype "passive"))
      (node (ref "JP10") (pin "3") (pinfunction "3_3") (pintype "passive"))
      (node (ref "JP10") (pin "5") (pinfunction "5_5") (pintype "passive"))
      (node (ref "JP10") (pin "7") (pinfunction "7_7") (pintype "passive"))
      (node (ref "JP11") (pin "1") (pinfunction "1_1") (pintype "passive"))
      (node (ref "JP11") (pin "3") (pinfunction "3_3") (pintype "passive"))
      (node (ref "JP11") (pin "5") (pinfunction "5_5") (pintype "passive"))
      (node (ref "JP11") (pin "7") (pinfunction "7_7") (pintype "passive"))
      (node (ref "JP7") (pin "1") (pinfunction "1_1") (pintype "passive"))
      (node (ref "K1") (pin "1") (pinfunction "NO1_1") (pintype "passive"))
      (node (ref "LCD1") (pin "17") (pinfunction "~{RESET}_17") (pintype "passive"))
      (node (ref "LCD1") (pin "19") (pinfunction "LED+_19") (pintype "passive"))
      (node (ref "LCD1") (pin "2") (pinfunction "VCC_2") (pintype "passive"))
      (node (ref "LCD2") (pin "15") (pinfunction "Anode_15") (pintype "passive"))
      (node (ref "LCD2") (pin "2") (pinfunction "VDD_2") (pintype "passive"))
      (node (ref "LS1") (pin "1") (pinfunction "A_1") (pintype "passive"))
      (node (ref "R4") (pin "1") (pinfunction "1_1") (pintype "passive"))
      (node (ref "R5") (pin "1") (pinfunction "1_1") (pintype "passive"))
      (node (ref "R6") (pin "1") (pinfunction "1_1") (pintype "passive"))
      (node (ref "R8") (pin "1") (pinfunction "BOT_1") (pintype "passive"))
      (node (ref "SW1") (pin "1") (pintype "passive"))
      (node (ref "U1") (pin "8") (pinfunction "VCC_8") (pintype "passive"))
      (node (ref "U2") (pin "16") (pinfunction "VCC_16") (pintype "passive"))
      (node (ref "U3") (pin "3") (pinfunction "VDD_3") (pintype "power_in"))
      (node (ref "U4") (pin "31") (pinfunction "EA/VPP_31") (pintype "passive"))
      (node (ref "U4") (pin "40") (pinfunction "VCC_40") (pintype "power_in"))
    )
    (net (code "65") (name "VCC_USB") (class "Default")
      (node (ref "C6") (pin "1") (pinfunction "1_1") (pintype "passive"))
      (node (ref "CN1") (pin "1") (pinfunction "VBUS_1") (pintype "power_in"))
      (node (ref "JP4") (pin "1") (pinfunction "1_1") (pintype "passive"))
      (node (ref "JP4") (pin "2") (pinfunction "2_2") (pintype "passive"))
      (node (ref "K1") (pin "2") (pinfunction "COMMON1_2") (pintype "passive"))
    )
    (net (code "66") (name "unconnected-(K1-COMMON2-Pad5)") (class "Default")
      (node (ref "K1") (pin "5") (pinfunction "COMMON2_5") (pintype "passive"))
    )
    (net (code "67") (name "unconnected-(K1-NC1-Pad3)") (class "Default")
      (node (ref "K1") (pin "3") (pinfunction "NC1_3") (pintype "passive"))
    )
    (net (code "68") (name "unconnected-(K1-NC2-Pad6)") (class "Default")
      (node (ref "K1") (pin "6") (pinfunction "NC2_6") (pintype "passive"))
    )
    (net (code "69") (name "unconnected-(K1-NO2-Pad4)") (class "Default")
      (node (ref "K1") (pin "4") (pinfunction "NO2_4") (pintype "passive"))
    )
    (net (code "70") (name "unconnected-(LCD1-GND-Pad16)") (class "Default")
      (node (ref "LCD1") (pin "16") (pinfunction "GND_16") (pintype "passive+no_connect"))
    )
    (net (code "71") (name "unconnected-(LCD1-NC-Pad18)") (class "Default")
      (node (ref "LCD1") (pin "18") (pinfunction "NC_18") (pintype "passive+no_connect"))
    )
    (net (code "72") (name "unconnected-(U2-CTS#-Pad9)") (class "Default")
      (node (ref "U2") (pin "9") (pinfunction "CTS#_9") (pintype "passive+no_connect"))
    )
    (net (code "73") (name "unconnected-(U2-DCD#-Pad12)") (class "Default")
      (node (ref "U2") (pin "12") (pinfunction "DCD#_12") (pintype "passive+no_connect"))
    )
    (net (code "74") (name "unconnected-(U2-DSR#-Pad10)") (class "Default")
      (node (ref "U2") (pin "10") (pinfunction "DSR#_10") (pintype "passive+no_connect"))
    )
    (net (code "75") (name "unconnected-(U2-DTR#-Pad13)") (class "Default")
      (node (ref "U2") (pin "13") (pinfunction "DTR#_13") (pintype "passive+no_connect"))
    )
    (net (code "76") (name "unconnected-(U2-R232-Pad15)") (class "Default")
      (node (ref "U2") (pin "15") (pinfunction "R232_15") (pintype "passive+no_connect"))
    )
    (net (code "77") (name "unconnected-(U2-RI#-Pad11)") (class "Default")
      (node (ref "U2") (pin "11") (pinfunction "RI#_11") (pintype "passive+no_connect"))
    )
    (net (code "78") (name "unconnected-(U2-RTS#-Pad14)") (class "Default")
      (node (ref "U2") (pin "14") (pinfunction "RTS#_14") (pintype "passive+no_connect"))
    )
  )
)
